# Adafruit_PowerBoost_500_Basic.net
KiCad netlist of a schematic drawn in EAGLE
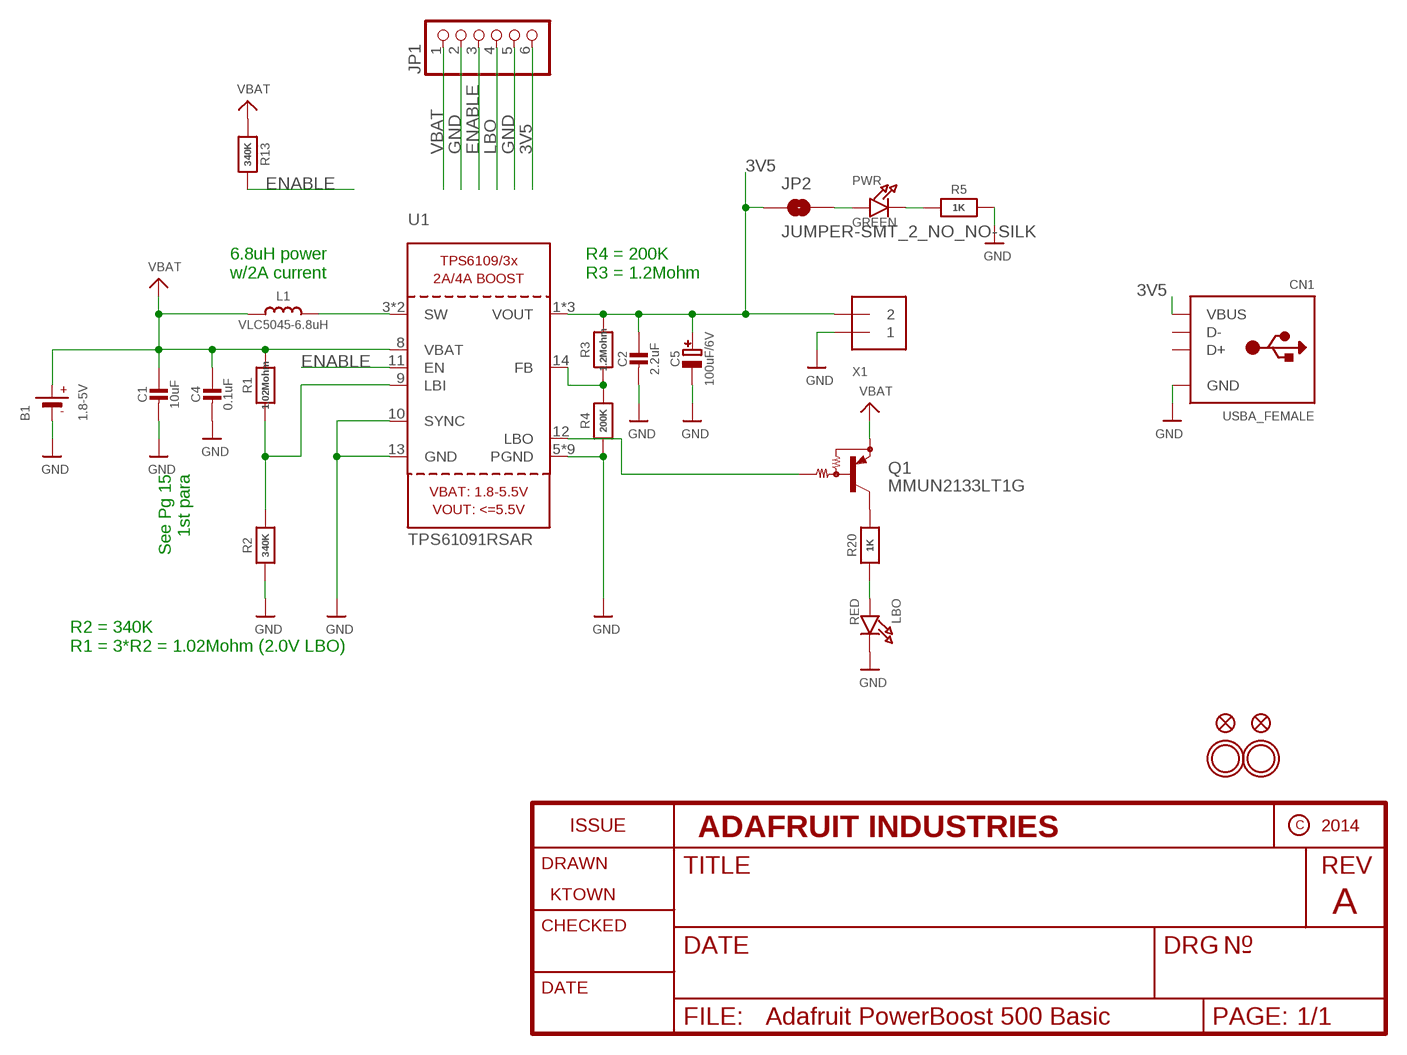
[diagram p0: schematic, sheet 1]

(export (version "E")
  (design (tool "Eeschema 10.0.6"))
  (components
    (comp (ref "B1")
      (value "1.8-5V")
      (footprint "eagle-import:JSTPH2")
      (libsource (lib "eagle-import") (part "BATTERY"))
    )
    (comp (ref "C1")
      (value "10uF")
      (footprint "eagle-import:0805-NO")
      (libsource (lib "eagle-import") (part "CAP_CERAMIC0805-NOOUTLINE"))
    )
    (comp (ref "C2")
      (value "2.2uF")
      (footprint "eagle-import:0805-NO")
      (libsource (lib "eagle-import") (part "CAP_CERAMIC0805-NOOUTLINE"))
    )
    (comp (ref "C4")
      (value "0.1uF")
      (footprint "eagle-import:0805-NO")
      (libsource (lib "eagle-import") (part "CAP_CERAMIC0805-NOOUTLINE"))
    )
    (comp (ref "C5")
      (value "100uF/6V")
      (footprint "eagle-import:EIA3528-21_B-R")
      (libsource (lib "eagle-import") (part "CAP_TANTALUMB/3528_REFLOW"))
    )
    (comp (ref "CN1")
      (value "USBA_FEMALE")
      (footprint "eagle-import:USB_HOST-PTH")
      (libsource (lib "eagle-import") (part "USB_TYPEAPTHFML"))
    )
    (comp (ref "FID2")
      (value "FIDUCIAL\"\"")
      (footprint "eagle-import:FIDUCIAL_1MM")
      (libsource (lib "eagle-import") (part "FIDUCIAL{dblquote}{dblquote}"))
    )
    (comp (ref "FID3")
      (value "FIDUCIAL\"\"")
      (footprint "eagle-import:FIDUCIAL_1MM")
      (fields (field (name "BOM") "EXCLUDE"))
      (libsource (lib "eagle-import") (part "FIDUCIAL{dblquote}{dblquote}"))
    )
    (comp (ref "JP1")
      (value "PINHD-1X6CB")
      (footprint "eagle-import:1X06-CLEANBIG")
      (libsource (lib "eagle-import") (part "PINHD-1X6CB"))
    )
    (comp (ref "JP2")
      (value "JUMPER-SMT_2_NO_NO-SILK")
      (footprint "eagle-import:SMT-JUMPER_2_NO_NO-SILK")
      (libsource (lib "eagle-import") (part "JUMPER-SMT_2_NO_NO-SILK"))
    )
    (comp (ref "L1")
      (value "VLC5045-6.8uH")
      (footprint "eagle-import:INDUCTOR_5X5MM_TDK_VLC5045")
      (libsource (lib "eagle-import") (part "INDUCTORTDK_VLC5045"))
    )
    (comp (ref "LBO")
      (value "RED")
      (footprint "eagle-import:CHIPLED_0805_NOOUTLINE")
      (libsource (lib "eagle-import") (part "LED0805_NOOUTLINE"))
    )
    (comp (ref "PWR")
      (value "GREEN")
      (footprint "eagle-import:CHIPLED_0805_NOOUTLINE")
      (libsource (lib "eagle-import") (part "LED0805_NOOUTLINE"))
    )
    (comp (ref "Q1")
      (value "MMUN2133LT1G")
      (footprint "eagle-import:SC59-BEC")
      (libsource (lib "eagle-import") (part "-PNP_DRIVER-SC59-BECMUN2114T1"))
    )
    (comp (ref "R1")
      (value "1.02Mohm")
      (footprint "eagle-import:0805-NO")
      (libsource (lib "eagle-import") (part "RESISTOR0805_NOOUTLINE"))
    )
    (comp (ref "R2")
      (value "340K")
      (footprint "eagle-import:0805-NO")
      (libsource (lib "eagle-import") (part "RESISTOR0805_NOOUTLINE"))
    )
    (comp (ref "R3")
      (value "1.2Mohm")
      (footprint "eagle-import:0805-NO")
      (libsource (lib "eagle-import") (part "RESISTOR0805_NOOUTLINE"))
    )
    (comp (ref "R4")
      (value "200K")
      (footprint "eagle-import:0805-NO")
      (libsource (lib "eagle-import") (part "RESISTOR0805_NOOUTLINE"))
    )
    (comp (ref "R5")
      (value "1K")
      (footprint "eagle-import:0805-NO")
      (libsource (lib "eagle-import") (part "RESISTOR0805_NOOUTLINE"))
    )
    (comp (ref "R13")
      (value "340K")
      (footprint "eagle-import:0805-NO")
      (libsource (lib "eagle-import") (part "RESISTOR0805_NOOUTLINE"))
    )
    (comp (ref "R20")
      (value "1K")
      (footprint "eagle-import:0805-NO")
      (libsource (lib "eagle-import") (part "RESISTOR0805_NOOUTLINE"))
    )
    (comp (ref "U$10")
      (value "MOUNTINGHOLE2.5")
      (footprint "eagle-import:MOUNTINGHOLE_2.5_PLATED")
      (libsource (lib "eagle-import") (part "MOUNTINGHOLE2.5"))
    )
    (comp (ref "U$12")
      (value "MOUNTINGHOLE2.5")
      (footprint "eagle-import:MOUNTINGHOLE_2.5_PLATED")
      (libsource (lib "eagle-import") (part "MOUNTINGHOLE2.5"))
    )
    (comp (ref "U1")
      (value "TPS61091RSAR")
      (footprint "eagle-import:PVQFN-16")
      (libsource (lib "eagle-import") (part "VREG_TPS6103X"))
    )
    (comp (ref "X1")
      (value "TERMBLOCK_1X2")
      (footprint "eagle-import:TERMBLOCK_1X2-3.5MM")
      (libsource (lib "eagle-import") (part "TERMBLOCK_1X2"))
    )
  )
  (nets
    (net (code "1") (name "/3V5") (class "Default")
      (node (ref "C2") (pin "1") (pinfunction "1_1") (pintype "passive"))
      (node (ref "C5") (pin "+") (pinfunction "+_+") (pintype "passive"))
      (node (ref "CN1") (pin "VBUS") (pinfunction "VBUS_VBUS") (pintype "power_in"))
      (node (ref "JP1") (pin "6") (pinfunction "6_6") (pintype "passive"))
      (node (ref "JP2") (pin "1") (pinfunction "1_1") (pintype "passive"))
      (node (ref "R3") (pin "2") (pinfunction "2_2") (pintype "passive"))
      (node (ref "U1") (pin "1") (pinfunction "VOUT_1") (pintype "power_in"))
      (node (ref "U1") (pin "15") (pinfunction "VOUT_15") (pintype "power_in"))
      (node (ref "U1") (pin "16") (pinfunction "VOUT_16") (pintype "power_in"))
      (node (ref "X1") (pin "2") (pinfunction "2_2") (pintype "passive"))
    )
    (net (code "2") (name "/ENABLE") (class "Default")
      (node (ref "JP1") (pin "3") (pinfunction "3_3") (pintype "passive"))
      (node (ref "R13") (pin "2") (pinfunction "2_2") (pintype "passive"))
      (node (ref "U1") (pin "11") (pinfunction "EN_11") (pintype "input"))
    )
    (net (code "3") (name "/LBO") (class "Default")
      (node (ref "JP1") (pin "4") (pinfunction "4_4") (pintype "passive"))
      (node (ref "Q1") (pin "B") (pinfunction "B_B") (pintype "passive"))
      (node (ref "U1") (pin "12") (pinfunction "LBO_12") (pintype "output"))
    )
    (net (code "4") (name "GND") (class "Default")
      (node (ref "B1") (pin "1") (pinfunction "-_1") (pintype "passive"))
      (node (ref "C1") (pin "2") (pinfunction "2_2") (pintype "passive"))
      (node (ref "C2") (pin "2") (pinfunction "2_2") (pintype "passive"))
      (node (ref "C4") (pin "2") (pinfunction "2_2") (pintype "passive"))
      (node (ref "C5") (pin "-") (pinfunction "-_-") (pintype "passive"))
      (node (ref "CN1") (pin "GND") (pinfunction "GND_GND") (pintype "power_in"))
      (node (ref "JP1") (pin "2") (pinfunction "2_2") (pintype "passive"))
      (node (ref "JP1") (pin "5") (pinfunction "5_5") (pintype "passive"))
      (node (ref "LBO") (pin "C") (pinfunction "C_C") (pintype "passive"))
      (node (ref "R2") (pin "1") (pinfunction "1_1") (pintype "passive"))
      (node (ref "R4") (pin "1") (pinfunction "1_1") (pintype "passive"))
      (node (ref "R5") (pin "2") (pinfunction "2_2") (pintype "passive"))
      (node (ref "U1") (pin "10") (pinfunction "SYNC_10") (pintype "input"))
      (node (ref "U1") (pin "13") (pinfunction "GND_13") (pintype "power_in"))
      (node (ref "U1") (pin "5") (pinfunction "PGND_5") (pintype "power_in"))
      (node (ref "U1") (pin "6") (pinfunction "PGND_6") (pintype "power_in"))
      (node (ref "U1") (pin "7") (pinfunction "PGND_7") (pintype "power_in"))
      (node (ref "U1") (pin "P$18") (pinfunction "PGND_P$18") (pintype "power_in"))
      (node (ref "U1") (pin "P$19") (pinfunction "PGND_P$19") (pintype "power_in"))
      (node (ref "U1") (pin "P$20") (pinfunction "PGND_P$20") (pintype "power_in"))
      (node (ref "U1") (pin "P$21") (pinfunction "PGND_P$21") (pintype "power_in"))
      (node (ref "U1") (pin "P$22") (pinfunction "PGND_P$22") (pintype "power_in"))
      (node (ref "U1") (pin "THERMAL") (pinfunction "PGND_THERMAL") (pintype "power_in"))
      (node (ref "X1") (pin "1") (pinfunction "1_1") (pintype "passive"))
    )
    (net (code "5") (name "Net-(JP2-Pad2)") (class "Default")
      (node (ref "JP2") (pin "2") (pinfunction "2_2") (pintype "passive"))
      (node (ref "PWR") (pin "A") (pinfunction "A_A") (pintype "passive"))
    )
    (net (code "6") (name "Net-(L1-2)") (class "Default")
      (node (ref "L1") (pin "P$2") (pinfunction "2_P$2") (pintype "passive"))
      (node (ref "U1") (pin "3") (pinfunction "SW_3") (pintype "input"))
      (node (ref "U1") (pin "4") (pinfunction "SW_4") (pintype "input"))
    )
    (net (code "7") (name "Net-(LBO-PadA)") (class "Default")
      (node (ref "LBO") (pin "A") (pinfunction "A_A") (pintype "passive"))
      (node (ref "R20") (pin "1") (pinfunction "1_1") (pintype "passive"))
    )
    (net (code "8") (name "Net-(PWR-PadC)") (class "Default")
      (node (ref "PWR") (pin "C") (pinfunction "C_C") (pintype "passive"))
      (node (ref "R5") (pin "1") (pinfunction "1_1") (pintype "passive"))
    )
    (net (code "9") (name "Net-(Q1-PadC)") (class "Default")
      (node (ref "Q1") (pin "C") (pinfunction "C_C") (pintype "passive"))
      (node (ref "R20") (pin "2") (pinfunction "2_2") (pintype "passive"))
    )
    (net (code "10") (name "Net-(U1-FB)") (class "Default")
      (node (ref "R3") (pin "1") (pinfunction "1_1") (pintype "passive"))
      (node (ref "R4") (pin "2") (pinfunction "2_2") (pintype "passive"))
      (node (ref "U1") (pin "14") (pinfunction "FB_14") (pintype "input"))
    )
    (net (code "11") (name "Net-(U1-LBI)") (class "Default")
      (node (ref "R1") (pin "1") (pinfunction "1_1") (pintype "passive"))
      (node (ref "R2") (pin "2") (pinfunction "2_2") (pintype "passive"))
      (node (ref "U1") (pin "9") (pinfunction "LBI_9") (pintype "input"))
    )
    (net (code "12") (name "VBAT") (class "Default")
      (node (ref "B1") (pin "2") (pinfunction "+_2") (pintype "passive"))
      (node (ref "C1") (pin "1") (pinfunction "1_1") (pintype "passive"))
      (node (ref "C4") (pin "1") (pinfunction "1_1") (pintype "passive"))
      (node (ref "JP1") (pin "1") (pinfunction "1_1") (pintype "passive"))
      (node (ref "L1") (pin "P$1") (pinfunction "1_P$1") (pintype "passive"))
      (node (ref "Q1") (pin "E") (pinfunction "E_E") (pintype "passive"))
      (node (ref "R1") (pin "2") (pinfunction "2_2") (pintype "passive"))
      (node (ref "R13") (pin "1") (pinfunction "1_1") (pintype "passive"))
      (node (ref "U1") (pin "8") (pinfunction "VBAT_8") (pintype "input"))
    )
    (net (code "13") (name "unconnected-(CN1-PadD+)") (class "Default")
      (node (ref "CN1") (pin "D+") (pinfunction "D+_D+") (pintype "bidirectional"))
    )
    (net (code "14") (name "unconnected-(CN1-PadD-)") (class "Default")
      (node (ref "CN1") (pin "D-") (pinfunction "D-_D-") (pintype "bidirectional"))
    )
  )
)
